# FPGA_bank13_14.net
KiCad netlist of a schematic drawn in Altium Designer
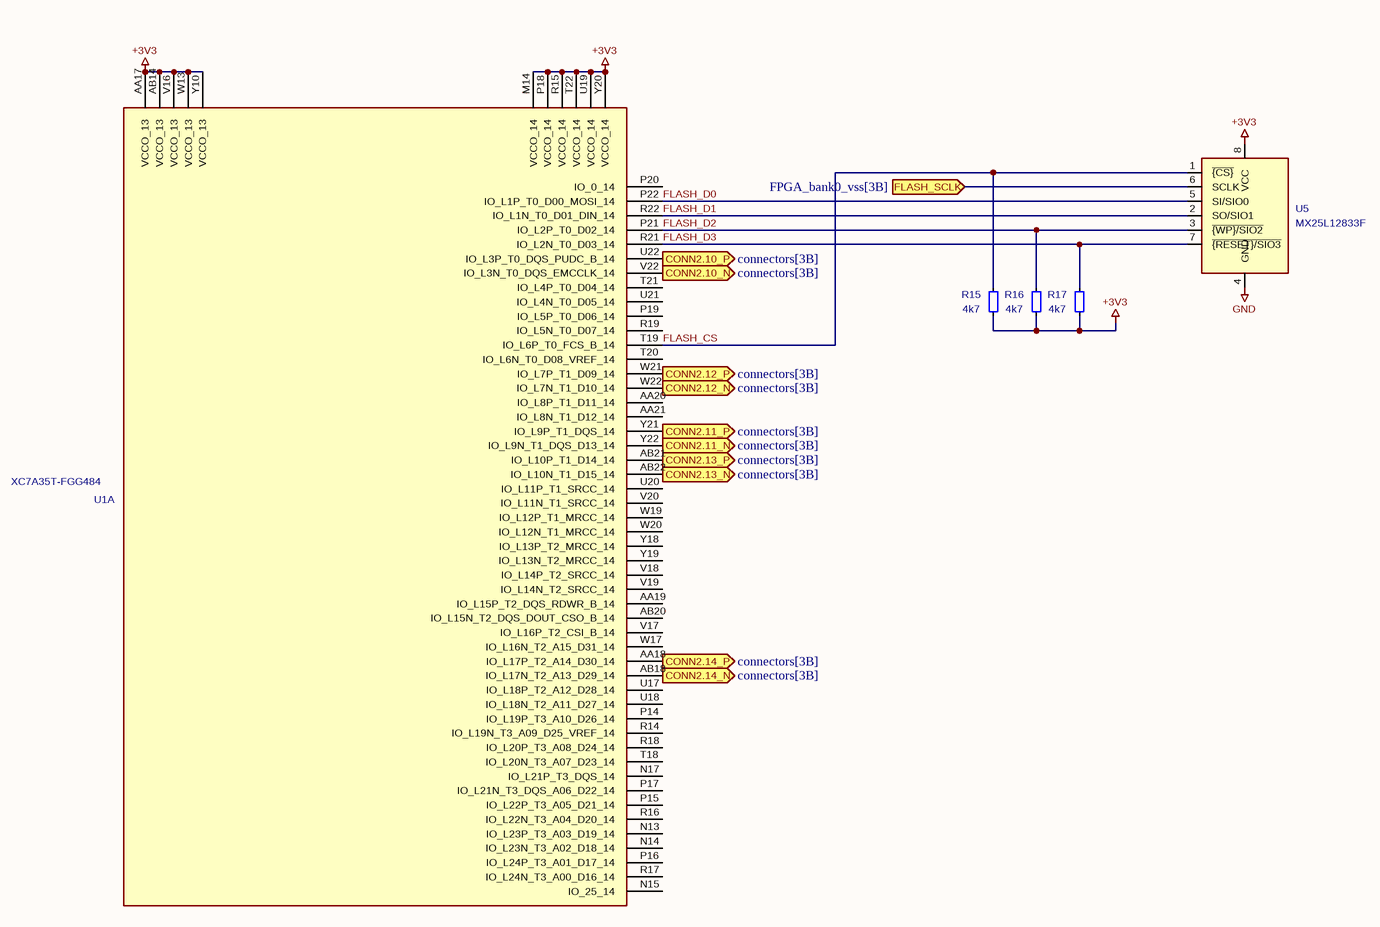
[diagram p0: FPGA_bank13_14.SchDoc]

(export (version "E")
  (design (tool "Eeschema 10.0.6"))
  (components
    (comp (ref "R15") (value "4k7") (libsource (lib "Device") (part "R_Small")))
    (comp (ref "R16") (value "4k7") (libsource (lib "Device") (part "R_Small")))
    (comp (ref "R17") (value "4k7") (libsource (lib "Device") (part "R_Small")))
    (comp (ref "U1")
      (value "XC7A35T-FGG484")
      (footprint "FB-BGA-484_23.0x23.0mm_Layout22x22_P1.0mm")
      (libsource (lib "som_fpga") (part "XC7A35T-FGG484"))
    )
    (comp (ref "U5") (value "MX25L12833F") (libsource (lib "Memory_Flash") (part "MX25R3235FM2xx0")))
  )
  (nets
    (net (code "1") (name "+3V3") (class "Default")
      (node (ref "R15") (pin "1") (pinfunction "1_1") (pintype "passive"))
      (node (ref "R16") (pin "1") (pinfunction "1_1") (pintype "passive"))
      (node (ref "R17") (pin "1") (pinfunction "1_1") (pintype "passive"))
      (node (ref "U1") (pin "AA17") (pinfunction "VCCO_13_AA17") (pintype "passive"))
      (node (ref "U1") (pin "AB14") (pinfunction "VCCO_13_AB14") (pintype "passive"))
      (node (ref "U1") (pin "M14") (pinfunction "VCCO_14_M14") (pintype "passive"))
      (node (ref "U1") (pin "P18") (pinfunction "VCCO_14_P18") (pintype "passive"))
      (node (ref "U1") (pin "R15") (pinfunction "VCCO_14_R15") (pintype "passive"))
      (node (ref "U1") (pin "T22") (pinfunction "VCCO_14_T22") (pintype "passive"))
      (node (ref "U1") (pin "U19") (pinfunction "VCCO_14_U19") (pintype "passive"))
      (node (ref "U1") (pin "V16") (pinfunction "VCCO_13_V16") (pintype "passive"))
      (node (ref "U1") (pin "W13") (pinfunction "VCCO_13_W13") (pintype "passive"))
      (node (ref "U1") (pin "Y10") (pinfunction "VCCO_13_Y10") (pintype "passive"))
      (node (ref "U1") (pin "Y20") (pinfunction "VCCO_14_Y20") (pintype "passive"))
      (node (ref "U5") (pin "8") (pinfunction "VCC_8") (pintype "passive"))
    )
    (net (code "2") (name "/CONN2.10_N") (class "Default")
      (node (ref "U1") (pin "V22") (pinfunction "IO_L3N_T0_DQS_EMCCLK_14_V22") (pintype "passive"))
    )
    (net (code "3") (name "/CONN2.10_P") (class "Default")
      (node (ref "U1") (pin "U22") (pinfunction "IO_L3P_T0_DQS_PUDC_B_14_U22") (pintype "passive"))
    )
    (net (code "4") (name "/CONN2.11_N") (class "Default")
      (node (ref "U1") (pin "Y22") (pinfunction "IO_L9N_T1_DQS_D13_14_Y22") (pintype "passive"))
    )
    (net (code "5") (name "/CONN2.11_P") (class "Default")
      (node (ref "U1") (pin "Y21") (pinfunction "IO_L9P_T1_DQS_14_Y21") (pintype "passive"))
    )
    (net (code "6") (name "/CONN2.12_N") (class "Default")
      (node (ref "U1") (pin "W22") (pinfunction "IO_L7N_T1_D10_14_W22") (pintype "passive"))
    )
    (net (code "7") (name "/CONN2.12_P") (class "Default")
      (node (ref "U1") (pin "W21") (pinfunction "IO_L7P_T1_D09_14_W21") (pintype "passive"))
    )
    (net (code "8") (name "/CONN2.13_N") (class "Default")
      (node (ref "U1") (pin "AB22") (pinfunction "IO_L10N_T1_D15_14_AB22") (pintype "passive"))
    )
    (net (code "9") (name "/CONN2.13_P") (class "Default")
      (node (ref "U1") (pin "AB21") (pinfunction "IO_L10P_T1_D14_14_AB21") (pintype "passive"))
    )
    (net (code "10") (name "/CONN2.14_N") (class "Default")
      (node (ref "U1") (pin "AB18") (pinfunction "IO_L17N_T2_A13_D29_14_AB18") (pintype "passive"))
    )
    (net (code "11") (name "/CONN2.14_P") (class "Default")
      (node (ref "U1") (pin "AA18") (pinfunction "IO_L17P_T2_A14_D30_14_AA18") (pintype "passive"))
    )
    (net (code "12") (name "/FLASH_CS") (class "Default")
      (node (ref "R15") (pin "2") (pinfunction "2_2") (pintype "passive"))
      (node (ref "U1") (pin "T19") (pinfunction "IO_L6P_T0_FCS_B_14_T19") (pintype "passive"))
      (node (ref "U5") (pin "1") (pinfunction "~{{CS}}_1") (pintype "passive"))
    )
    (net (code "13") (name "/FLASH_D0") (class "Default")
      (node (ref "U1") (pin "P22") (pinfunction "IO_L1P_T0_D00_MOSI_14_P22") (pintype "passive"))
      (node (ref "U5") (pin "5") (pinfunction "SI/SIO0_5") (pintype "passive"))
    )
    (net (code "14") (name "/FLASH_D1") (class "Default")
      (node (ref "U1") (pin "R22") (pinfunction "IO_L1N_T0_D01_DIN_14_R22") (pintype "passive"))
      (node (ref "U5") (pin "2") (pinfunction "SO/SIO1_2") (pintype "passive"))
    )
    (net (code "15") (name "/FLASH_D2") (class "Default")
      (node (ref "R16") (pin "2") (pinfunction "2_2") (pintype "passive"))
      (node (ref "U1") (pin "P21") (pinfunction "IO_L2P_T0_D02_14_P21") (pintype "passive"))
      (node (ref "U5") (pin "3") (pinfunction "~{{WP}/SIO2}_3") (pintype "passive"))
    )
    (net (code "16") (name "/FLASH_D3") (class "Default")
      (node (ref "R17") (pin "2") (pinfunction "2_2") (pintype "passive"))
      (node (ref "U1") (pin "R21") (pinfunction "IO_L2N_T0_D03_14_R21") (pintype "passive"))
      (node (ref "U5") (pin "7") (pinfunction "~{{RESET}/SIO3}_7") (pintype "passive"))
    )
    (net (code "17") (name "/FLASH_SCLK") (class "Default")
      (node (ref "U5") (pin "6") (pinfunction "SCLK_6") (pintype "passive"))
    )
    (net (code "18") (name "GND") (class "Default")
      (node (ref "U5") (pin "4") (pinfunction "GND_4") (pintype "passive"))
    )
    (net (code "19") (name "unconnected-(U1A-IO_0_14-PadP20)") (class "Default")
      (node (ref "U1") (pin "P20") (pinfunction "IO_0_14_P20") (pintype "passive"))
    )
    (net (code "20") (name "unconnected-(U1A-IO_25_14-PadN15)") (class "Default")
      (node (ref "U1") (pin "N15") (pinfunction "IO_25_14_N15") (pintype "passive"))
    )
    (net (code "21") (name "unconnected-(U1A-IO_L4N_T0_D05_14-PadU21)") (class "Default")
      (node (ref "U1") (pin "U21") (pinfunction "IO_L4N_T0_D05_14_U21") (pintype "passive"))
    )
    (net (code "22") (name "unconnected-(U1A-IO_L4P_T0_D04_14-PadT21)") (class "Default")
      (node (ref "U1") (pin "T21") (pinfunction "IO_L4P_T0_D04_14_T21") (pintype "passive"))
    )
    (net (code "23") (name "unconnected-(U1A-IO_L5N_T0_D07_14-PadR19)") (class "Default")
      (node (ref "U1") (pin "R19") (pinfunction "IO_L5N_T0_D07_14_R19") (pintype "passive"))
    )
    (net (code "24") (name "unconnected-(U1A-IO_L5P_T0_D06_14-PadP19)") (class "Default")
      (node (ref "U1") (pin "P19") (pinfunction "IO_L5P_T0_D06_14_P19") (pintype "passive"))
    )
    (net (code "25") (name "unconnected-(U1A-IO_L6N_T0_D08_VREF_14-PadT20)") (class "Default")
      (node (ref "U1") (pin "T20") (pinfunction "IO_L6N_T0_D08_VREF_14_T20") (pintype "passive"))
    )
    (net (code "26") (name "unconnected-(U1A-IO_L8N_T1_D12_14-PadAA21)") (class "Default")
      (node (ref "U1") (pin "AA21") (pinfunction "IO_L8N_T1_D12_14_AA21") (pintype "passive"))
    )
    (net (code "27") (name "unconnected-(U1A-IO_L8P_T1_D11_14-PadAA20)") (class "Default")
      (node (ref "U1") (pin "AA20") (pinfunction "IO_L8P_T1_D11_14_AA20") (pintype "passive"))
    )
    (net (code "28") (name "unconnected-(U1A-IO_L11N_T1_SRCC_14-PadV20)") (class "Default")
      (node (ref "U1") (pin "V20") (pinfunction "IO_L11N_T1_SRCC_14_V20") (pintype "passive"))
    )
    (net (code "29") (name "unconnected-(U1A-IO_L11P_T1_SRCC_14-PadU20)") (class "Default")
      (node (ref "U1") (pin "U20") (pinfunction "IO_L11P_T1_SRCC_14_U20") (pintype "passive"))
    )
    (net (code "30") (name "unconnected-(U1A-IO_L12N_T1_MRCC_14-PadW20)") (class "Default")
      (node (ref "U1") (pin "W20") (pinfunction "IO_L12N_T1_MRCC_14_W20") (pintype "passive"))
    )
    (net (code "31") (name "unconnected-(U1A-IO_L12P_T1_MRCC_14-PadW19)") (class "Default")
      (node (ref "U1") (pin "W19") (pinfunction "IO_L12P_T1_MRCC_14_W19") (pintype "passive"))
    )
    (net (code "32") (name "unconnected-(U1A-IO_L13N_T2_MRCC_14-PadY19)") (class "Default")
      (node (ref "U1") (pin "Y19") (pinfunction "IO_L13N_T2_MRCC_14_Y19") (pintype "passive"))
    )
    (net (code "33") (name "unconnected-(U1A-IO_L13P_T2_MRCC_14-PadY18)") (class "Default")
      (node (ref "U1") (pin "Y18") (pinfunction "IO_L13P_T2_MRCC_14_Y18") (pintype "passive"))
    )
    (net (code "34") (name "unconnected-(U1A-IO_L14N_T2_SRCC_14-PadV19)") (class "Default")
      (node (ref "U1") (pin "V19") (pinfunction "IO_L14N_T2_SRCC_14_V19") (pintype "passive"))
    )
    (net (code "35") (name "unconnected-(U1A-IO_L14P_T2_SRCC_14-PadV18)") (class "Default")
      (node (ref "U1") (pin "V18") (pinfunction "IO_L14P_T2_SRCC_14_V18") (pintype "passive"))
    )
    (net (code "36") (name "unconnected-(U1A-IO_L15N_T2_DQS_DOUT_CSO_B_14-PadAB20)") (class "Default")
      (node (ref "U1") (pin "AB20") (pinfunction "IO_L15N_T2_DQS_DOUT_CSO_B_14_AB20") (pintype "passive"))
    )
    (net (code "37") (name "unconnected-(U1A-IO_L15P_T2_DQS_RDWR_B_14-PadAA19)") (class "Default")
      (node (ref "U1") (pin "AA19") (pinfunction "IO_L15P_T2_DQS_RDWR_B_14_AA19") (pintype "passive"))
    )
    (net (code "38") (name "unconnected-(U1A-IO_L16N_T2_A15_D31_14-PadW17)") (class "Default")
      (node (ref "U1") (pin "W17") (pinfunction "IO_L16N_T2_A15_D31_14_W17") (pintype "passive"))
    )
    (net (code "39") (name "unconnected-(U1A-IO_L16P_T2_CSI_B_14-PadV17)") (class "Default")
      (node (ref "U1") (pin "V17") (pinfunction "IO_L16P_T2_CSI_B_14_V17") (pintype "passive"))
    )
    (net (code "40") (name "unconnected-(U1A-IO_L18N_T2_A11_D27_14-PadU18)") (class "Default")
      (node (ref "U1") (pin "U18") (pinfunction "IO_L18N_T2_A11_D27_14_U18") (pintype "passive"))
    )
    (net (code "41") (name "unconnected-(U1A-IO_L18P_T2_A12_D28_14-PadU17)") (class "Default")
      (node (ref "U1") (pin "U17") (pinfunction "IO_L18P_T2_A12_D28_14_U17") (pintype "passive"))
    )
    (net (code "42") (name "unconnected-(U1A-IO_L19N_T3_A09_D25_VREF_14-PadR14)") (class "Default")
      (node (ref "U1") (pin "R14") (pinfunction "IO_L19N_T3_A09_D25_VREF_14_R14") (pintype "passive"))
    )
    (net (code "43") (name "unconnected-(U1A-IO_L19P_T3_A10_D26_14-PadP14)") (class "Default")
      (node (ref "U1") (pin "P14") (pinfunction "IO_L19P_T3_A10_D26_14_P14") (pintype "passive"))
    )
    (net (code "44") (name "unconnected-(U1A-IO_L20N_T3_A07_D23_14-PadT18)") (class "Default")
      (node (ref "U1") (pin "T18") (pinfunction "IO_L20N_T3_A07_D23_14_T18") (pintype "passive"))
    )
    (net (code "45") (name "unconnected-(U1A-IO_L20P_T3_A08_D24_14-PadR18)") (class "Default")
      (node (ref "U1") (pin "R18") (pinfunction "IO_L20P_T3_A08_D24_14_R18") (pintype "passive"))
    )
    (net (code "46") (name "unconnected-(U1A-IO_L21N_T3_DQS_A06_D22_14-PadP17)") (class "Default")
      (node (ref "U1") (pin "P17") (pinfunction "IO_L21N_T3_DQS_A06_D22_14_P17") (pintype "passive"))
    )
    (net (code "47") (name "unconnected-(U1A-IO_L21P_T3_DQS_14-PadN17)") (class "Default")
      (node (ref "U1") (pin "N17") (pinfunction "IO_L21P_T3_DQS_14_N17") (pintype "passive"))
    )
    (net (code "48") (name "unconnected-(U1A-IO_L22N_T3_A04_D20_14-PadR16)") (class "Default")
      (node (ref "U1") (pin "R16") (pinfunction "IO_L22N_T3_A04_D20_14_R16") (pintype "passive"))
    )
    (net (code "49") (name "unconnected-(U1A-IO_L22P_T3_A05_D21_14-PadP15)") (class "Default")
      (node (ref "U1") (pin "P15") (pinfunction "IO_L22P_T3_A05_D21_14_P15") (pintype "passive"))
    )
    (net (code "50") (name "unconnected-(U1A-IO_L23N_T3_A02_D18_14-PadN14)") (class "Default")
      (node (ref "U1") (pin "N14") (pinfunction "IO_L23N_T3_A02_D18_14_N14") (pintype "passive"))
    )
    (net (code "51") (name "unconnected-(U1A-IO_L23P_T3_A03_D19_14-PadN13)") (class "Default")
      (node (ref "U1") (pin "N13") (pinfunction "IO_L23P_T3_A03_D19_14_N13") (pintype "passive"))
    )
    (net (code "52") (name "unconnected-(U1A-IO_L24N_T3_A00_D16_14-PadR17)") (class "Default")
      (node (ref "U1") (pin "R17") (pinfunction "IO_L24N_T3_A00_D16_14_R17") (pintype "passive"))
    )
    (net (code "53") (name "unconnected-(U1A-IO_L24P_T3_A01_D17_14-PadP16)") (class "Default")
      (node (ref "U1") (pin "P16") (pinfunction "IO_L24P_T3_A01_D17_14_P16") (pintype "passive"))
    )
  )
)
